# Sheet1.net
KiCad netlist of a schematic drawn in Altium Designer
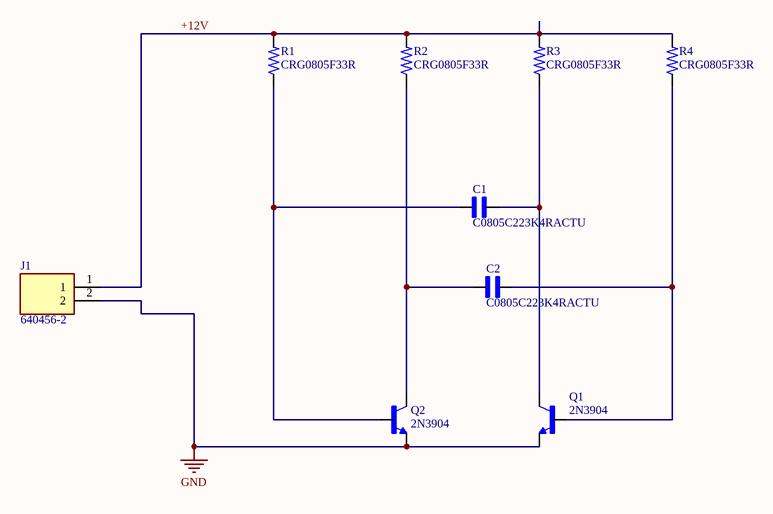
[diagram p0: Sheet1.SchDoc]

(export (version "E")
  (design (tool "Eeschema 10.0.6"))
  (components
    (comp (ref "C1")
      (value "C0805C223K4RACTU")
      (footprint "CAPC2012X88N")
      (description "Capacitor, Ceramic, 22nF, 16VDC, 10-% Tol, 10+% Tol, X7R-TC Code, -15, 15%-TC")
      (fields (field (name "MF") "KEMET"))
      (libsource (lib "C0805C223K4RACTU") (part "C0805C223K4RACTU"))
    )
    (comp (ref "C2")
      (value "C0805C223K4RACTU")
      (footprint "CAPC2012X88N")
      (description "Capacitor, Ceramic, 22nF, 16VDC, 10-% Tol, 10+% Tol, X7R-TC Code, -15, 15%-TC")
      (fields (field (name "MF") "KEMET"))
      (libsource (lib "C0805C223K4RACTU") (part "C0805C223K4RACTU"))
    )
    (comp (ref "J1")
      (value "640456-2")
      (footprint "TE_640456-2")
      (description "Header Friction Lock MTA-100 2 250 VAC Polyester Tin Copper Alloy Tin ¦ TE Connectivity 640456-2")
      (fields (field (name "MF") "TE Connectivity"))
      (libsource (lib "header") (part "640456-2"))
    )
    (comp (ref "Q1")
      (value "2N3904")
      (footprint "TO92254P460H750-3")
      (description "BJT, TO-92, 40V, 200mA, NPN, 0.625W, 150Â°C")
      (fields (field (name "MF") "Diotec Semiconductor"))
      (libsource (lib "2N3904") (part "2N3904"))
    )
    (comp (ref "Q2")
      (value "2N3904")
      (footprint "TO92254P460H750-3")
      (description "BJT, TO-92, 40V, 200mA, NPN, 0.625W, 150Â°C")
      (fields (field (name "MF") "Diotec Semiconductor"))
      (libsource (lib "") (part "2N3904_1"))
    )
    (comp (ref "R1")
      (value "CRG0805F33R")
      (footprint "RESC2012X65N")
      (description "Fixed Resistors")
      (fields (field (name "MF") "TE Connectivity"))
      (libsource (lib "CRG0805F33R") (part "CRG0805F33R"))
    )
    (comp (ref "R2")
      (value "CRG0805F33R")
      (footprint "RESC2012X65N")
      (description "Fixed Resistors")
      (fields (field (name "MF") "TE Connectivity"))
      (libsource (lib "CRG0805F33R") (part "CRG0805F33R"))
    )
    (comp (ref "R3")
      (value "CRG0805F33R")
      (footprint "RESC2012X65N")
      (description "Fixed Resistors")
      (fields (field (name "MF") "TE Connectivity"))
      (libsource (lib "CRG0805F33R") (part "CRG0805F33R"))
    )
    (comp (ref "R4")
      (value "CRG0805F33R")
      (footprint "RESC2012X65N")
      (description "Fixed Resistors")
      (fields (field (name "MF") "TE Connectivity"))
      (libsource (lib "CRG0805F33R") (part "CRG0805F33R"))
    )
  )
  (nets
    (net (code "1") (name "/+12V") (class "Default")
      (node (ref "J1") (pin "1") (pinfunction "1_1") (pintype "passive"))
      (node (ref "R1") (pin "2") (pinfunction "2_2") (pintype "passive"))
      (node (ref "R2") (pin "2") (pinfunction "2_2") (pintype "passive"))
      (node (ref "R3") (pin "2") (pinfunction "2_2") (pintype "passive"))
      (node (ref "R4") (pin "2") (pinfunction "2_2") (pintype "passive"))
    )
    (net (code "2") (name "GND") (class "Default")
      (node (ref "J1") (pin "2") (pinfunction "2_2") (pintype "passive"))
      (node (ref "Q1") (pin "1") (pinfunction "E_1") (pintype "passive"))
      (node (ref "Q2") (pin "1") (pinfunction "E_1") (pintype "passive"))
    )
    (net (code "3") (name "Net-(Q1-B)") (class "Default")
      (node (ref "C2") (pin "1") (pinfunction "1_1") (pintype "passive"))
      (node (ref "Q1") (pin "2") (pinfunction "B_2") (pintype "passive"))
      (node (ref "R4") (pin "1") (pinfunction "1_1") (pintype "passive"))
    )
    (net (code "4") (name "Net-(Q1-C)") (class "Default")
      (node (ref "C1") (pin "1") (pinfunction "1_1") (pintype "passive"))
      (node (ref "Q1") (pin "3") (pinfunction "C_3") (pintype "passive"))
      (node (ref "R3") (pin "1") (pinfunction "1_1") (pintype "passive"))
    )
    (net (code "5") (name "Net-(Q2-B)") (class "Default")
      (node (ref "C1") (pin "2") (pinfunction "2_2") (pintype "passive"))
      (node (ref "Q2") (pin "2") (pinfunction "B_2") (pintype "passive"))
      (node (ref "R1") (pin "1") (pinfunction "1_1") (pintype "passive"))
    )
    (net (code "6") (name "Net-(Q2-C)") (class "Default")
      (node (ref "C2") (pin "2") (pinfunction "2_2") (pintype "passive"))
      (node (ref "Q2") (pin "3") (pinfunction "C_3") (pintype "passive"))
      (node (ref "R2") (pin "1") (pinfunction "1_1") (pintype "passive"))
    )
  )
)
